# schaltplan.net
KiCad netlist of a schematic drawn in EAGLE
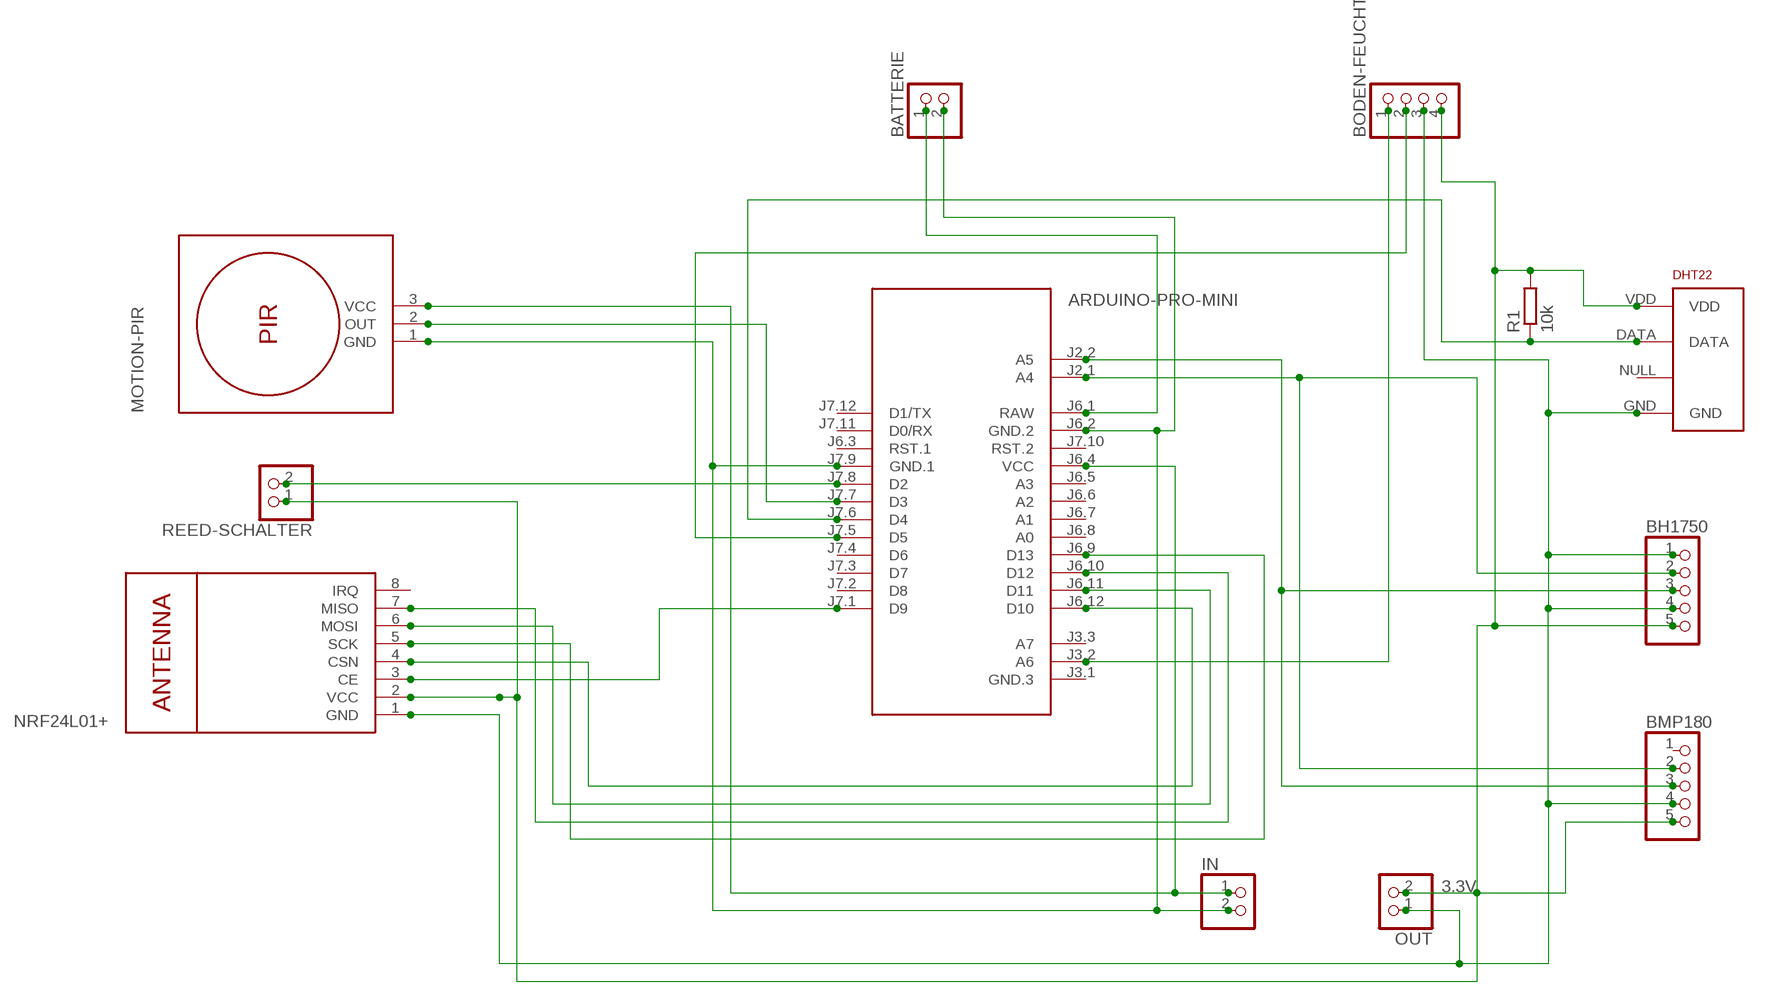
[diagram p0: schematic, sheet 1]

(export (version "E")
  (design (tool "Eeschema 10.0.6"))
  (components
    (comp (ref "ARDUINO-PRO-MINI")
      (value "ARDUINO-PRO-MINI-5.0V#NP")
      (footprint "eagle-import:ARDUINO-PRO-MINI#NP")
      (libsource (lib "eagle-import") (part "ARDUINO-PRO-MINI-#NP5.0V"))
    )
    (comp (ref "BATTERIE")
      (value "PINHD-1X2")
      (footprint "eagle-import:1X02")
      (libsource (lib "eagle-import") (part "PINHD-1X2"))
    )
    (comp (ref "BH1750")
      (value "PINHD-1X5")
      (footprint "eagle-import:1X05")
      (libsource (lib "eagle-import") (part "PINHD-1X5"))
    )
    (comp (ref "BMP180")
      (value "PINHD-1X5")
      (footprint "eagle-import:1X05")
      (libsource (lib "eagle-import") (part "PINHD-1X5"))
    )
    (comp (ref "BODEN-FEUCHT")
      (value "PINHD-1X4")
      (footprint "eagle-import:1X04")
      (libsource (lib "eagle-import") (part "PINHD-1X4"))
    )
    (comp (ref "DHT22")
      (value "RHT03_DHT-22_AM2302")
      (footprint "eagle-import:RHT03_DHT-22")
      (libsource (lib "eagle-import") (part "RHT03_DHT-22_AM2302"))
    )
    (comp (ref "IN")
      (value "PINHD-1X2")
      (footprint "eagle-import:1X02")
      (libsource (lib "eagle-import") (part "PINHD-1X2"))
    )
    (comp (ref "MOTION-PIR")
      (value "MOTION-PIR-DYP-ME003")
      (footprint "eagle-import:MOTION-PIR-DYP-ME003")
      (libsource (lib "eagle-import") (part "MOTION-PIR-DYP-ME003"))
    )
    (comp (ref "NRF24L01+")
      (value "WIRELESS-NRF24L01")
      (footprint "eagle-import:WIRELESS-NRF24L01")
      (libsource (lib "eagle-import") (part "WIRELESS-NRF24L01"))
    )
    (comp (ref "OUT")
      (value "PINHD-1X2")
      (footprint "eagle-import:1X02")
      (libsource (lib "eagle-import") (part "PINHD-1X2"))
    )
    (comp (ref "R1")
      (value "10k")
      (footprint "eagle-import:0207_10")
      (libsource (lib "eagle-import") (part "R-EU_0207/10"))
    )
    (comp (ref "REED-SCHALTER")
      (value "PINHD-1X2")
      (footprint "eagle-import:1X02")
      (libsource (lib "eagle-import") (part "PINHD-1X2"))
    )
  )
  (nets
    (net (code "1") (name "/3.3V") (class "Default")
      (node (ref "BH1750") (pin "5") (pinfunction "5_5") (pintype "passive"))
      (node (ref "BMP180") (pin "5") (pinfunction "5_5") (pintype "passive"))
      (node (ref "BODEN-FEUCHT") (pin "4") (pinfunction "4_4") (pintype "passive"))
      (node (ref "DHT22") (pin "VDD") (pinfunction "VDD_VDD") (pintype "power_in"))
      (node (ref "NRF24L01+") (pin "2") (pinfunction "VCC_2") (pintype "power_in"))
      (node (ref "OUT") (pin "2") (pinfunction "2_2") (pintype "passive"))
      (node (ref "R1") (pin "2") (pinfunction "2_2") (pintype "passive"))
      (node (ref "REED-SCHALTER") (pin "1") (pinfunction "1_1") (pintype "passive"))
    )
    (net (code "2") (name "/GND") (class "Default")
      (node (ref "ARDUINO-PRO-MINI") (pin "J6.2") (pinfunction "GND.2_J6.2") (pintype "power_in"))
      (node (ref "ARDUINO-PRO-MINI") (pin "J7.9") (pinfunction "GND.1_J7.9") (pintype "power_in"))
      (node (ref "BATTERIE") (pin "2") (pinfunction "2_2") (pintype "passive"))
      (node (ref "BH1750") (pin "1") (pinfunction "1_1") (pintype "passive"))
      (node (ref "BH1750") (pin "4") (pinfunction "4_4") (pintype "passive"))
      (node (ref "BMP180") (pin "4") (pinfunction "4_4") (pintype "passive"))
      (node (ref "BODEN-FEUCHT") (pin "3") (pinfunction "3_3") (pintype "passive"))
      (node (ref "DHT22") (pin "GND") (pinfunction "GND_GND") (pintype "power_in"))
      (node (ref "IN") (pin "2") (pinfunction "2_2") (pintype "passive"))
      (node (ref "MOTION-PIR") (pin "1") (pinfunction "GND_1") (pintype "power_in"))
      (node (ref "NRF24L01+") (pin "1") (pinfunction "GND_1") (pintype "power_in"))
      (node (ref "OUT") (pin "1") (pinfunction "1_1") (pintype "passive"))
    )
    (net (code "3") (name "Net-(ARDUINO-PRO-MINI-A4)") (class "Default")
      (node (ref "ARDUINO-PRO-MINI") (pin "J2.1") (pinfunction "A4_J2.1") (pintype "bidirectional"))
      (node (ref "BH1750") (pin "2") (pinfunction "2_2") (pintype "passive"))
      (node (ref "BMP180") (pin "2") (pinfunction "2_2") (pintype "passive"))
    )
    (net (code "4") (name "Net-(ARDUINO-PRO-MINI-A5)") (class "Default")
      (node (ref "ARDUINO-PRO-MINI") (pin "J2.2") (pinfunction "A5_J2.2") (pintype "bidirectional"))
      (node (ref "BH1750") (pin "3") (pinfunction "3_3") (pintype "passive"))
      (node (ref "BMP180") (pin "3") (pinfunction "3_3") (pintype "passive"))
    )
    (net (code "5") (name "Net-(ARDUINO-PRO-MINI-A6)") (class "Default")
      (node (ref "ARDUINO-PRO-MINI") (pin "J3.2") (pinfunction "A6_J3.2") (pintype "bidirectional"))
      (node (ref "BODEN-FEUCHT") (pin "1") (pinfunction "1_1") (pintype "passive"))
    )
    (net (code "6") (name "Net-(ARDUINO-PRO-MINI-D2)") (class "Default")
      (node (ref "ARDUINO-PRO-MINI") (pin "J7.8") (pinfunction "D2_J7.8") (pintype "bidirectional"))
      (node (ref "REED-SCHALTER") (pin "2") (pinfunction "2_2") (pintype "passive"))
    )
    (net (code "7") (name "Net-(ARDUINO-PRO-MINI-D3)") (class "Default")
      (node (ref "ARDUINO-PRO-MINI") (pin "J7.7") (pinfunction "D3_J7.7") (pintype "bidirectional"))
      (node (ref "MOTION-PIR") (pin "2") (pinfunction "OUT_2") (pintype "output"))
    )
    (net (code "8") (name "Net-(ARDUINO-PRO-MINI-D4)") (class "Default")
      (node (ref "ARDUINO-PRO-MINI") (pin "J7.6") (pinfunction "D4_J7.6") (pintype "bidirectional"))
      (node (ref "DHT22") (pin "DATA") (pinfunction "DATA_DATA") (pintype "bidirectional"))
      (node (ref "R1") (pin "1") (pinfunction "1_1") (pintype "passive"))
    )
    (net (code "9") (name "Net-(ARDUINO-PRO-MINI-D5)") (class "Default")
      (node (ref "ARDUINO-PRO-MINI") (pin "J7.5") (pinfunction "D5_J7.5") (pintype "bidirectional"))
      (node (ref "BODEN-FEUCHT") (pin "2") (pinfunction "2_2") (pintype "passive"))
    )
    (net (code "10") (name "Net-(ARDUINO-PRO-MINI-D9)") (class "Default")
      (node (ref "ARDUINO-PRO-MINI") (pin "J7.1") (pinfunction "D9_J7.1") (pintype "bidirectional"))
      (node (ref "NRF24L01+") (pin "3") (pinfunction "CE_3") (pintype "bidirectional"))
    )
    (net (code "11") (name "Net-(ARDUINO-PRO-MINI-D10)") (class "Default")
      (node (ref "ARDUINO-PRO-MINI") (pin "J6.12") (pinfunction "D10_J6.12") (pintype "bidirectional"))
      (node (ref "NRF24L01+") (pin "4") (pinfunction "CSN_4") (pintype "bidirectional"))
    )
    (net (code "12") (name "Net-(ARDUINO-PRO-MINI-D11)") (class "Default")
      (node (ref "ARDUINO-PRO-MINI") (pin "J6.11") (pinfunction "D11_J6.11") (pintype "bidirectional"))
      (node (ref "NRF24L01+") (pin "6") (pinfunction "MOSI_6") (pintype "bidirectional"))
    )
    (net (code "13") (name "Net-(ARDUINO-PRO-MINI-D12)") (class "Default")
      (node (ref "ARDUINO-PRO-MINI") (pin "J6.10") (pinfunction "D12_J6.10") (pintype "bidirectional"))
      (node (ref "NRF24L01+") (pin "7") (pinfunction "MISO_7") (pintype "bidirectional"))
    )
    (net (code "14") (name "Net-(ARDUINO-PRO-MINI-D13)") (class "Default")
      (node (ref "ARDUINO-PRO-MINI") (pin "J6.9") (pinfunction "D13_J6.9") (pintype "bidirectional"))
      (node (ref "NRF24L01+") (pin "5") (pinfunction "SCK_5") (pintype "bidirectional"))
    )
    (net (code "15") (name "Net-(ARDUINO-PRO-MINI-RAW)") (class "Default")
      (node (ref "ARDUINO-PRO-MINI") (pin "J6.1") (pinfunction "RAW_J6.1") (pintype "power_in"))
      (node (ref "BATTERIE") (pin "1") (pinfunction "1_1") (pintype "passive"))
    )
    (net (code "16") (name "Net-(ARDUINO-PRO-MINI-VCC)") (class "Default")
      (node (ref "ARDUINO-PRO-MINI") (pin "J6.4") (pinfunction "VCC_J6.4") (pintype "power_in"))
      (node (ref "IN") (pin "1") (pinfunction "1_1") (pintype "passive"))
      (node (ref "MOTION-PIR") (pin "3") (pinfunction "VCC_3") (pintype "power_in"))
    )
    (net (code "17") (name "unconnected-(ARDUINO-PRO-MINI-A0-PadJ6.8)") (class "Default")
      (node (ref "ARDUINO-PRO-MINI") (pin "J6.8") (pinfunction "A0_J6.8") (pintype "bidirectional"))
    )
    (net (code "18") (name "unconnected-(ARDUINO-PRO-MINI-A1-PadJ6.7)") (class "Default")
      (node (ref "ARDUINO-PRO-MINI") (pin "J6.7") (pinfunction "A1_J6.7") (pintype "bidirectional"))
    )
    (net (code "19") (name "unconnected-(ARDUINO-PRO-MINI-A2-PadJ6.6)") (class "Default")
      (node (ref "ARDUINO-PRO-MINI") (pin "J6.6") (pinfunction "A2_J6.6") (pintype "bidirectional"))
    )
    (net (code "20") (name "unconnected-(ARDUINO-PRO-MINI-A3-PadJ6.5)") (class "Default")
      (node (ref "ARDUINO-PRO-MINI") (pin "J6.5") (pinfunction "A3_J6.5") (pintype "bidirectional"))
    )
    (net (code "21") (name "unconnected-(ARDUINO-PRO-MINI-A7-PadJ3.3)") (class "Default")
      (node (ref "ARDUINO-PRO-MINI") (pin "J3.3") (pinfunction "A7_J3.3") (pintype "bidirectional"))
    )
    (net (code "22") (name "unconnected-(ARDUINO-PRO-MINI-D0{slash}RX-PadJ7.11)") (class "Default")
      (node (ref "ARDUINO-PRO-MINI") (pin "J7.11") (pinfunction "D0/RX_J7.11") (pintype "bidirectional"))
    )
    (net (code "23") (name "unconnected-(ARDUINO-PRO-MINI-D1{slash}TX-PadJ7.12)") (class "Default")
      (node (ref "ARDUINO-PRO-MINI") (pin "J7.12") (pinfunction "D1/TX_J7.12") (pintype "bidirectional"))
    )
    (net (code "24") (name "unconnected-(ARDUINO-PRO-MINI-D6-PadJ7.4)") (class "Default")
      (node (ref "ARDUINO-PRO-MINI") (pin "J7.4") (pinfunction "D6_J7.4") (pintype "bidirectional"))
    )
    (net (code "25") (name "unconnected-(ARDUINO-PRO-MINI-D7-PadJ7.3)") (class "Default")
      (node (ref "ARDUINO-PRO-MINI") (pin "J7.3") (pinfunction "D7_J7.3") (pintype "bidirectional"))
    )
    (net (code "26") (name "unconnected-(ARDUINO-PRO-MINI-D8-PadJ7.2)") (class "Default")
      (node (ref "ARDUINO-PRO-MINI") (pin "J7.2") (pinfunction "D8_J7.2") (pintype "bidirectional"))
    )
    (net (code "27") (name "unconnected-(ARDUINO-PRO-MINI-GND.3-PadJ3.1)") (class "Default")
      (node (ref "ARDUINO-PRO-MINI") (pin "J3.1") (pinfunction "GND.3_J3.1") (pintype "bidirectional"))
    )
    (net (code "28") (name "unconnected-(ARDUINO-PRO-MINI-RST.1-PadJ6.3)") (class "Default")
      (node (ref "ARDUINO-PRO-MINI") (pin "J6.3") (pinfunction "RST.1_J6.3") (pintype "bidirectional"))
    )
    (net (code "29") (name "unconnected-(ARDUINO-PRO-MINI-RST.2-PadJ7.10)") (class "Default")
      (node (ref "ARDUINO-PRO-MINI") (pin "J7.10") (pinfunction "RST.2_J7.10") (pintype "bidirectional"))
    )
    (net (code "30") (name "unconnected-(BMP180-Pad1)") (class "Default")
      (node (ref "BMP180") (pin "1") (pinfunction "1_1") (pintype "passive"))
    )
    (net (code "31") (name "unconnected-(DHT22-PadNULL)") (class "Default")
      (node (ref "DHT22") (pin "NULL") (pinfunction "NULL_NULL") (pintype "no_connect"))
    )
    (net (code "32") (name "unconnected-(NRF24L01+-IRQ-Pad8)") (class "Default")
      (node (ref "NRF24L01+") (pin "8") (pinfunction "IRQ_8") (pintype "bidirectional"))
    )
  )
)
